# Dice_RGB_-_Sht_2.net
KiCad netlist of a schematic drawn in Altium Designer
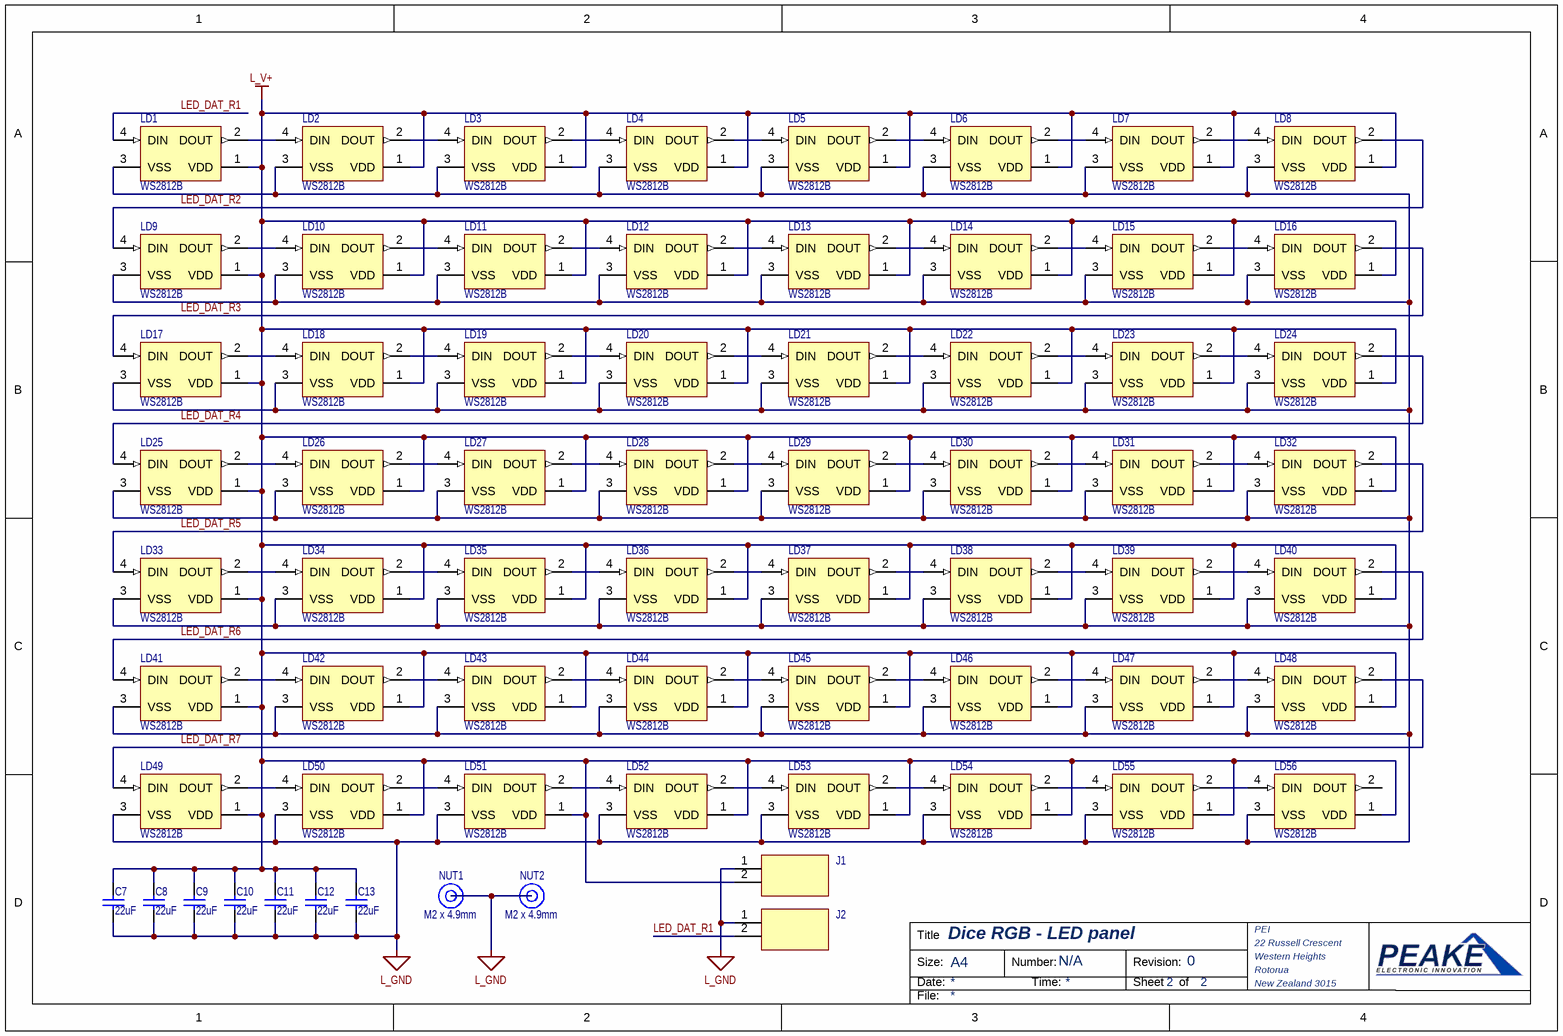
[diagram p0: Dice RGB - Sht 2.SchDoc]

(export (version "E")
  (design (tool "Eeschema 10.0.6"))
  (components
    (comp (ref "C7")
      (value "22uF")
      (footprint "0805_CAP")
      (description "SMD Capacitor")
      (fields (field (name "Comment") "Capacitor"))
      (libsource (lib "Peake Electronic Innovation") (part "Capacitor"))
    )
    (comp (ref "C8")
      (value "22uF")
      (footprint "0805_CAP")
      (description "SMD Capacitor")
      (fields (field (name "Comment") "Capacitor"))
      (libsource (lib "Peake Electronic Innovation") (part "Capacitor"))
    )
    (comp (ref "C9")
      (value "22uF")
      (footprint "0805_CAP")
      (description "SMD Capacitor")
      (fields (field (name "Comment") "Capacitor"))
      (libsource (lib "Peake Electronic Innovation") (part "Capacitor"))
    )
    (comp (ref "C10")
      (value "22uF")
      (footprint "0805_CAP")
      (description "SMD Capacitor")
      (fields (field (name "Comment") "Capacitor"))
      (libsource (lib "Peake Electronic Innovation") (part "Capacitor"))
    )
    (comp (ref "C11")
      (value "22uF")
      (footprint "0805_CAP")
      (description "SMD Capacitor")
      (fields (field (name "Comment") "Capacitor"))
      (libsource (lib "Peake Electronic Innovation") (part "Capacitor"))
    )
    (comp (ref "C12")
      (value "22uF")
      (footprint "0805_CAP")
      (description "SMD Capacitor")
      (fields (field (name "Comment") "Capacitor"))
      (libsource (lib "Peake Electronic Innovation") (part "Capacitor"))
    )
    (comp (ref "C13")
      (value "22uF")
      (footprint "0805_CAP")
      (description "SMD Capacitor")
      (fields (field (name "Comment") "Capacitor"))
      (libsource (lib "Peake Electronic Innovation") (part "Capacitor"))
    )
    (comp (ref "J1")
      (value "2_Pin")
      (footprint "2P 2mm SMD dbl height male header")
      (description "2 Pin Connector")
      (libsource (lib "Peake Electronic Innovation") (part "2_Pin"))
    )
    (comp (ref "J2")
      (value "2_Pin")
      (footprint "2P 2mm SMD dbl height male header")
      (description "2 Pin Connector")
      (libsource (lib "Peake Electronic Innovation") (part "2_Pin"))
    )
    (comp (ref "LD1")
      (value "WS2812B")
      (footprint "WS2812B-2020")
      (fields (field (name "MANUFACTURER") "Adafruit Industries"))
      (libsource (lib "Peake Electronic Innovation") (part "ADAI-WS2812B-4"))
    )
    (comp (ref "LD2")
      (value "WS2812B")
      (footprint "WS2812B-2020")
      (fields (field (name "MANUFACTURER") "Adafruit Industries"))
      (libsource (lib "Peake Electronic Innovation") (part "ADAI-WS2812B-4"))
    )
    (comp (ref "LD3")
      (value "WS2812B")
      (footprint "WS2812B-2020")
      (fields (field (name "MANUFACTURER") "Adafruit Industries"))
      (libsource (lib "Peake Electronic Innovation") (part "ADAI-WS2812B-4"))
    )
    (comp (ref "LD4")
      (value "WS2812B")
      (footprint "WS2812B-2020")
      (fields (field (name "MANUFACTURER") "Adafruit Industries"))
      (libsource (lib "Peake Electronic Innovation") (part "ADAI-WS2812B-4"))
    )
    (comp (ref "LD5")
      (value "WS2812B")
      (footprint "WS2812B-2020")
      (fields (field (name "MANUFACTURER") "Adafruit Industries"))
      (libsource (lib "Peake Electronic Innovation") (part "ADAI-WS2812B-4"))
    )
    (comp (ref "LD6")
      (value "WS2812B")
      (footprint "WS2812B-2020")
      (fields (field (name "MANUFACTURER") "Adafruit Industries"))
      (libsource (lib "Peake Electronic Innovation") (part "ADAI-WS2812B-4"))
    )
    (comp (ref "LD7")
      (value "WS2812B")
      (footprint "WS2812B-2020")
      (fields (field (name "MANUFACTURER") "Adafruit Industries"))
      (libsource (lib "Peake Electronic Innovation") (part "ADAI-WS2812B-4"))
    )
    (comp (ref "LD8")
      (value "WS2812B")
      (footprint "WS2812B-2020")
      (fields (field (name "MANUFACTURER") "Adafruit Industries"))
      (libsource (lib "Peake Electronic Innovation") (part "ADAI-WS2812B-4"))
    )
    (comp (ref "LD9")
      (value "WS2812B")
      (footprint "WS2812B-2020")
      (fields (field (name "MANUFACTURER") "Adafruit Industries"))
      (libsource (lib "Peake Electronic Innovation") (part "ADAI-WS2812B-4"))
    )
    (comp (ref "LD10")
      (value "WS2812B")
      (footprint "WS2812B-2020")
      (fields (field (name "MANUFACTURER") "Adafruit Industries"))
      (libsource (lib "Peake Electronic Innovation") (part "ADAI-WS2812B-4"))
    )
    (comp (ref "LD11")
      (value "WS2812B")
      (footprint "WS2812B-2020")
      (fields (field (name "MANUFACTURER") "Adafruit Industries"))
      (libsource (lib "Peake Electronic Innovation") (part "ADAI-WS2812B-4"))
    )
    (comp (ref "LD12")
      (value "WS2812B")
      (footprint "WS2812B-2020")
      (fields (field (name "MANUFACTURER") "Adafruit Industries"))
      (libsource (lib "Peake Electronic Innovation") (part "ADAI-WS2812B-4"))
    )
    (comp (ref "LD13")
      (value "WS2812B")
      (footprint "WS2812B-2020")
      (fields (field (name "MANUFACTURER") "Adafruit Industries"))
      (libsource (lib "Peake Electronic Innovation") (part "ADAI-WS2812B-4"))
    )
    (comp (ref "LD14")
      (value "WS2812B")
      (footprint "WS2812B-2020")
      (fields (field (name "MANUFACTURER") "Adafruit Industries"))
      (libsource (lib "Peake Electronic Innovation") (part "ADAI-WS2812B-4"))
    )
    (comp (ref "LD15")
      (value "WS2812B")
      (footprint "WS2812B-2020")
      (fields (field (name "MANUFACTURER") "Adafruit Industries"))
      (libsource (lib "Peake Electronic Innovation") (part "ADAI-WS2812B-4"))
    )
    (comp (ref "LD16")
      (value "WS2812B")
      (footprint "WS2812B-2020")
      (fields (field (name "MANUFACTURER") "Adafruit Industries"))
      (libsource (lib "Peake Electronic Innovation") (part "ADAI-WS2812B-4"))
    )
    (comp (ref "LD17")
      (value "WS2812B")
      (footprint "WS2812B-2020")
      (fields (field (name "MANUFACTURER") "Adafruit Industries"))
      (libsource (lib "Peake Electronic Innovation") (part "ADAI-WS2812B-4"))
    )
    (comp (ref "LD18")
      (value "WS2812B")
      (footprint "WS2812B-2020")
      (fields (field (name "MANUFACTURER") "Adafruit Industries"))
      (libsource (lib "Peake Electronic Innovation") (part "ADAI-WS2812B-4"))
    )
    (comp (ref "LD19")
      (value "WS2812B")
      (footprint "WS2812B-2020")
      (fields (field (name "MANUFACTURER") "Adafruit Industries"))
      (libsource (lib "Peake Electronic Innovation") (part "ADAI-WS2812B-4"))
    )
    (comp (ref "LD20")
      (value "WS2812B")
      (footprint "WS2812B-2020")
      (fields (field (name "MANUFACTURER") "Adafruit Industries"))
      (libsource (lib "Peake Electronic Innovation") (part "ADAI-WS2812B-4"))
    )
    (comp (ref "LD21")
      (value "WS2812B")
      (footprint "WS2812B-2020")
      (fields (field (name "MANUFACTURER") "Adafruit Industries"))
      (libsource (lib "Peake Electronic Innovation") (part "ADAI-WS2812B-4"))
    )
    (comp (ref "LD22")
      (value "WS2812B")
      (footprint "WS2812B-2020")
      (fields (field (name "MANUFACTURER") "Adafruit Industries"))
      (libsource (lib "Peake Electronic Innovation") (part "ADAI-WS2812B-4"))
    )
    (comp (ref "LD23")
      (value "WS2812B")
      (footprint "WS2812B-2020")
      (fields (field (name "MANUFACTURER") "Adafruit Industries"))
      (libsource (lib "Peake Electronic Innovation") (part "ADAI-WS2812B-4"))
    )
    (comp (ref "LD24")
      (value "WS2812B")
      (footprint "WS2812B-2020")
      (fields (field (name "MANUFACTURER") "Adafruit Industries"))
      (libsource (lib "Peake Electronic Innovation") (part "ADAI-WS2812B-4"))
    )
    (comp (ref "LD25")
      (value "WS2812B")
      (footprint "WS2812B-2020")
      (fields (field (name "MANUFACTURER") "Adafruit Industries"))
      (libsource (lib "Peake Electronic Innovation") (part "ADAI-WS2812B-4"))
    )
    (comp (ref "LD26")
      (value "WS2812B")
      (footprint "WS2812B-2020")
      (fields (field (name "MANUFACTURER") "Adafruit Industries"))
      (libsource (lib "Peake Electronic Innovation") (part "ADAI-WS2812B-4"))
    )
    (comp (ref "LD27")
      (value "WS2812B")
      (footprint "WS2812B-2020")
      (fields (field (name "MANUFACTURER") "Adafruit Industries"))
      (libsource (lib "Peake Electronic Innovation") (part "ADAI-WS2812B-4"))
    )
    (comp (ref "LD28")
      (value "WS2812B")
      (footprint "WS2812B-2020")
      (fields (field (name "MANUFACTURER") "Adafruit Industries"))
      (libsource (lib "Peake Electronic Innovation") (part "ADAI-WS2812B-4"))
    )
    (comp (ref "LD29")
      (value "WS2812B")
      (footprint "WS2812B-2020")
      (fields (field (name "MANUFACTURER") "Adafruit Industries"))
      (libsource (lib "Peake Electronic Innovation") (part "ADAI-WS2812B-4"))
    )
    (comp (ref "LD30")
      (value "WS2812B")
      (footprint "WS2812B-2020")
      (fields (field (name "MANUFACTURER") "Adafruit Industries"))
      (libsource (lib "Peake Electronic Innovation") (part "ADAI-WS2812B-4"))
    )
    (comp (ref "LD31")
      (value "WS2812B")
      (footprint "WS2812B-2020")
      (fields (field (name "MANUFACTURER") "Adafruit Industries"))
      (libsource (lib "Peake Electronic Innovation") (part "ADAI-WS2812B-4"))
    )
    (comp (ref "LD32")
      (value "WS2812B")
      (footprint "WS2812B-2020")
      (fields (field (name "MANUFACTURER") "Adafruit Industries"))
      (libsource (lib "Peake Electronic Innovation") (part "ADAI-WS2812B-4"))
    )
    (comp (ref "LD33")
      (value "WS2812B")
      (footprint "WS2812B-2020")
      (fields (field (name "MANUFACTURER") "Adafruit Industries"))
      (libsource (lib "Peake Electronic Innovation") (part "ADAI-WS2812B-4"))
    )
    (comp (ref "LD34")
      (value "WS2812B")
      (footprint "WS2812B-2020")
      (fields (field (name "MANUFACTURER") "Adafruit Industries"))
      (libsource (lib "Peake Electronic Innovation") (part "ADAI-WS2812B-4"))
    )
    (comp (ref "LD35")
      (value "WS2812B")
      (footprint "WS2812B-2020")
      (fields (field (name "MANUFACTURER") "Adafruit Industries"))
      (libsource (lib "Peake Electronic Innovation") (part "ADAI-WS2812B-4"))
    )
    (comp (ref "LD36")
      (value "WS2812B")
      (footprint "WS2812B-2020")
      (fields (field (name "MANUFACTURER") "Adafruit Industries"))
      (libsource (lib "Peake Electronic Innovation") (part "ADAI-WS2812B-4"))
    )
    (comp (ref "LD37")
      (value "WS2812B")
      (footprint "WS2812B-2020")
      (fields (field (name "MANUFACTURER") "Adafruit Industries"))
      (libsource (lib "Peake Electronic Innovation") (part "ADAI-WS2812B-4"))
    )
    (comp (ref "LD38")
      (value "WS2812B")
      (footprint "WS2812B-2020")
      (fields (field (name "MANUFACTURER") "Adafruit Industries"))
      (libsource (lib "Peake Electronic Innovation") (part "ADAI-WS2812B-4"))
    )
    (comp (ref "LD39")
      (value "WS2812B")
      (footprint "WS2812B-2020")
      (fields (field (name "MANUFACTURER") "Adafruit Industries"))
      (libsource (lib "Peake Electronic Innovation") (part "ADAI-WS2812B-4"))
    )
    (comp (ref "LD40")
      (value "WS2812B")
      (footprint "WS2812B-2020")
      (fields (field (name "MANUFACTURER") "Adafruit Industries"))
      (libsource (lib "Peake Electronic Innovation") (part "ADAI-WS2812B-4"))
    )
    (comp (ref "LD41")
      (value "WS2812B")
      (footprint "WS2812B-2020")
      (fields (field (name "MANUFACTURER") "Adafruit Industries"))
      (libsource (lib "Peake Electronic Innovation") (part "ADAI-WS2812B-4"))
    )
    (comp (ref "LD42")
      (value "WS2812B")
      (footprint "WS2812B-2020")
      (fields (field (name "MANUFACTURER") "Adafruit Industries"))
      (libsource (lib "Peake Electronic Innovation") (part "ADAI-WS2812B-4"))
    )
    (comp (ref "LD43")
      (value "WS2812B")
      (footprint "WS2812B-2020")
      (fields (field (name "MANUFACTURER") "Adafruit Industries"))
      (libsource (lib "Peake Electronic Innovation") (part "ADAI-WS2812B-4"))
    )
    (comp (ref "LD44")
      (value "WS2812B")
      (footprint "WS2812B-2020")
      (fields (field (name "MANUFACTURER") "Adafruit Industries"))
      (libsource (lib "Peake Electronic Innovation") (part "ADAI-WS2812B-4"))
    )
    (comp (ref "LD45")
      (value "WS2812B")
      (footprint "WS2812B-2020")
      (fields (field (name "MANUFACTURER") "Adafruit Industries"))
      (libsource (lib "Peake Electronic Innovation") (part "ADAI-WS2812B-4"))
    )
    (comp (ref "LD46")
      (value "WS2812B")
      (footprint "WS2812B-2020")
      (fields (field (name "MANUFACTURER") "Adafruit Industries"))
      (libsource (lib "Peake Electronic Innovation") (part "ADAI-WS2812B-4"))
    )
    (comp (ref "LD47")
      (value "WS2812B")
      (footprint "WS2812B-2020")
      (fields (field (name "MANUFACTURER") "Adafruit Industries"))
      (libsource (lib "Peake Electronic Innovation") (part "ADAI-WS2812B-4"))
    )
    (comp (ref "LD48")
      (value "WS2812B")
      (footprint "WS2812B-2020")
      (fields (field (name "MANUFACTURER") "Adafruit Industries"))
      (libsource (lib "Peake Electronic Innovation") (part "ADAI-WS2812B-4"))
    )
    (comp (ref "LD49")
      (value "WS2812B")
      (footprint "WS2812B-2020")
      (fields (field (name "MANUFACTURER") "Adafruit Industries"))
      (libsource (lib "Peake Electronic Innovation") (part "ADAI-WS2812B-4"))
    )
    (comp (ref "LD50")
      (value "WS2812B")
      (footprint "WS2812B-2020")
      (fields (field (name "MANUFACTURER") "Adafruit Industries"))
      (libsource (lib "Peake Electronic Innovation") (part "ADAI-WS2812B-4"))
    )
    (comp (ref "LD51")
      (value "WS2812B")
      (footprint "WS2812B-2020")
      (fields (field (name "MANUFACTURER") "Adafruit Industries"))
      (libsource (lib "Peake Electronic Innovation") (part "ADAI-WS2812B-4"))
    )
    (comp (ref "LD52")
      (value "WS2812B")
      (footprint "WS2812B-2020")
      (fields (field (name "MANUFACTURER") "Adafruit Industries"))
      (libsource (lib "Peake Electronic Innovation") (part "ADAI-WS2812B-4"))
    )
    (comp (ref "LD53")
      (value "WS2812B")
      (footprint "WS2812B-2020")
      (fields (field (name "MANUFACTURER") "Adafruit Industries"))
      (libsource (lib "Peake Electronic Innovation") (part "ADAI-WS2812B-4"))
    )
    (comp (ref "LD54")
      (value "WS2812B")
      (footprint "WS2812B-2020")
      (fields (field (name "MANUFACTURER") "Adafruit Industries"))
      (libsource (lib "Peake Electronic Innovation") (part "ADAI-WS2812B-4"))
    )
    (comp (ref "LD55")
      (value "WS2812B")
      (footprint "WS2812B-2020")
      (fields (field (name "MANUFACTURER") "Adafruit Industries"))
      (libsource (lib "Peake Electronic Innovation") (part "ADAI-WS2812B-4"))
    )
    (comp (ref "LD56")
      (value "WS2812B")
      (footprint "WS2812B-2020")
      (fields (field (name "MANUFACTURER") "Adafruit Industries"))
      (libsource (lib "Peake Electronic Innovation") (part "ADAI-WS2812B-4"))
    )
    (comp (ref "NUT1")
      (value "M2 x 4.9mm")
      (footprint "PCB Nut M2-SMD")
      (description "SMD or through hole soldered PCB nut")
      (libsource (lib "Peake Electronic Innovation") (part "PCB Nut-Symbol-1"))
    )
    (comp (ref "NUT2")
      (value "M2 x 4.9mm")
      (footprint "PCB Nut M2-SMD")
      (description "SMD or through hole soldered PCB nut")
      (libsource (lib "Peake Electronic Innovation") (part "PCB Nut-Symbol-1"))
    )
  )
  (nets
    (net (code "1") (name "/LED_DAT_R1") (class "Default")
      (node (ref "J2") (pin "2") (pinfunction "V+_2") (pintype "passive"))
      (node (ref "LD1") (pin "4") (pinfunction "DIN_4") (pintype "input"))
    )
    (net (code "2") (name "/LED_DAT_R2") (class "Default")
      (node (ref "LD8") (pin "2") (pinfunction "DOUT_2") (pintype "output"))
      (node (ref "LD9") (pin "4") (pinfunction "DIN_4") (pintype "input"))
    )
    (net (code "3") (name "/LED_DAT_R3") (class "Default")
      (node (ref "LD16") (pin "2") (pinfunction "DOUT_2") (pintype "output"))
      (node (ref "LD17") (pin "4") (pinfunction "DIN_4") (pintype "input"))
    )
    (net (code "4") (name "/LED_DAT_R4") (class "Default")
      (node (ref "LD24") (pin "2") (pinfunction "DOUT_2") (pintype "output"))
      (node (ref "LD25") (pin "4") (pinfunction "DIN_4") (pintype "input"))
    )
    (net (code "5") (name "/LED_DAT_R5") (class "Default")
      (node (ref "LD32") (pin "2") (pinfunction "DOUT_2") (pintype "output"))
      (node (ref "LD33") (pin "4") (pinfunction "DIN_4") (pintype "input"))
    )
    (net (code "6") (name "/LED_DAT_R6") (class "Default")
      (node (ref "LD40") (pin "2") (pinfunction "DOUT_2") (pintype "output"))
      (node (ref "LD41") (pin "4") (pinfunction "DIN_4") (pintype "input"))
    )
    (net (code "7") (name "/LED_DAT_R7") (class "Default")
      (node (ref "LD48") (pin "2") (pinfunction "DOUT_2") (pintype "output"))
      (node (ref "LD49") (pin "4") (pinfunction "DIN_4") (pintype "input"))
    )
    (net (code "8") (name "L_GND") (class "Default")
      (node (ref "C10") (pin "1") (pinfunction "1_1") (pintype "passive"))
      (node (ref "C11") (pin "1") (pinfunction "1_1") (pintype "passive"))
      (node (ref "C12") (pin "1") (pinfunction "1_1") (pintype "passive"))
      (node (ref "C13") (pin "1") (pinfunction "1_1") (pintype "passive"))
      (node (ref "C7") (pin "1") (pinfunction "1_1") (pintype "passive"))
      (node (ref "C8") (pin "1") (pinfunction "1_1") (pintype "passive"))
      (node (ref "C9") (pin "1") (pinfunction "1_1") (pintype "passive"))
      (node (ref "J1") (pin "1") (pinfunction "GND_1") (pintype "passive"))
      (node (ref "J2") (pin "1") (pinfunction "GND_1") (pintype "passive"))
      (node (ref "LD1") (pin "3") (pinfunction "VSS_3") (pintype "power_in"))
      (node (ref "LD10") (pin "3") (pinfunction "VSS_3") (pintype "power_in"))
      (node (ref "LD11") (pin "3") (pinfunction "VSS_3") (pintype "power_in"))
      (node (ref "LD12") (pin "3") (pinfunction "VSS_3") (pintype "power_in"))
      (node (ref "LD13") (pin "3") (pinfunction "VSS_3") (pintype "power_in"))
      (node (ref "LD14") (pin "3") (pinfunction "VSS_3") (pintype "power_in"))
      (node (ref "LD15") (pin "3") (pinfunction "VSS_3") (pintype "power_in"))
      (node (ref "LD16") (pin "3") (pinfunction "VSS_3") (pintype "power_in"))
      (node (ref "LD17") (pin "3") (pinfunction "VSS_3") (pintype "power_in"))
      (node (ref "LD18") (pin "3") (pinfunction "VSS_3") (pintype "power_in"))
      (node (ref "LD19") (pin "3") (pinfunction "VSS_3") (pintype "power_in"))
      (node (ref "LD2") (pin "3") (pinfunction "VSS_3") (pintype "power_in"))
      (node (ref "LD20") (pin "3") (pinfunction "VSS_3") (pintype "power_in"))
      (node (ref "LD21") (pin "3") (pinfunction "VSS_3") (pintype "power_in"))
      (node (ref "LD22") (pin "3") (pinfunction "VSS_3") (pintype "power_in"))
      (node (ref "LD23") (pin "3") (pinfunction "VSS_3") (pintype "power_in"))
      (node (ref "LD24") (pin "3") (pinfunction "VSS_3") (pintype "power_in"))
      (node (ref "LD25") (pin "3") (pinfunction "VSS_3") (pintype "power_in"))
      (node (ref "LD26") (pin "3") (pinfunction "VSS_3") (pintype "power_in"))
      (node (ref "LD27") (pin "3") (pinfunction "VSS_3") (pintype "power_in"))
      (node (ref "LD28") (pin "3") (pinfunction "VSS_3") (pintype "power_in"))
      (node (ref "LD29") (pin "3") (pinfunction "VSS_3") (pintype "power_in"))
      (node (ref "LD3") (pin "3") (pinfunction "VSS_3") (pintype "power_in"))
      (node (ref "LD30") (pin "3") (pinfunction "VSS_3") (pintype "power_in"))
      (node (ref "LD31") (pin "3") (pinfunction "VSS_3") (pintype "power_in"))
      (node (ref "LD32") (pin "3") (pinfunction "VSS_3") (pintype "power_in"))
      (node (ref "LD33") (pin "3") (pinfunction "VSS_3") (pintype "power_in"))
      (node (ref "LD34") (pin "3") (pinfunction "VSS_3") (pintype "power_in"))
      (node (ref "LD35") (pin "3") (pinfunction "VSS_3") (pintype "power_in"))
      (node (ref "LD36") (pin "3") (pinfunction "VSS_3") (pintype "power_in"))
      (node (ref "LD37") (pin "3") (pinfunction "VSS_3") (pintype "power_in"))
      (node (ref "LD38") (pin "3") (pinfunction "VSS_3") (pintype "power_in"))
      (node (ref "LD39") (pin "3") (pinfunction "VSS_3") (pintype "power_in"))
      (node (ref "LD4") (pin "3") (pinfunction "VSS_3") (pintype "power_in"))
      (node (ref "LD40") (pin "3") (pinfunction "VSS_3") (pintype "power_in"))
      (node (ref "LD41") (pin "3") (pinfunction "VSS_3") (pintype "power_in"))
      (node (ref "LD42") (pin "3") (pinfunction "VSS_3") (pintype "power_in"))
      (node (ref "LD43") (pin "3") (pinfunction "VSS_3") (pintype "power_in"))
      (node (ref "LD44") (pin "3") (pinfunction "VSS_3") (pintype "power_in"))
      (node (ref "LD45") (pin "3") (pinfunction "VSS_3") (pintype "power_in"))
      (node (ref "LD46") (pin "3") (pinfunction "VSS_3") (pintype "power_in"))
      (node (ref "LD47") (pin "3") (pinfunction "VSS_3") (pintype "power_in"))
      (node (ref "LD48") (pin "3") (pinfunction "VSS_3") (pintype "power_in"))
      (node (ref "LD49") (pin "3") (pinfunction "VSS_3") (pintype "power_in"))
      (node (ref "LD5") (pin "3") (pinfunction "VSS_3") (pintype "power_in"))
      (node (ref "LD50") (pin "3") (pinfunction "VSS_3") (pintype "power_in"))
      (node (ref "LD51") (pin "3") (pinfunction "VSS_3") (pintype "power_in"))
      (node (ref "LD52") (pin "3") (pinfunction "VSS_3") (pintype "power_in"))
      (node (ref "LD53") (pin "3") (pinfunction "VSS_3") (pintype "power_in"))
      (node (ref "LD54") (pin "3") (pinfunction "VSS_3") (pintype "power_in"))
      (node (ref "LD55") (pin "3") (pinfunction "VSS_3") (pintype "power_in"))
      (node (ref "LD56") (pin "3") (pinfunction "VSS_3") (pintype "power_in"))
      (node (ref "LD6") (pin "3") (pinfunction "VSS_3") (pintype "power_in"))
      (node (ref "LD7") (pin "3") (pinfunction "VSS_3") (pintype "power_in"))
      (node (ref "LD8") (pin "3") (pinfunction "VSS_3") (pintype "power_in"))
      (node (ref "LD9") (pin "3") (pinfunction "VSS_3") (pintype "power_in"))
      (node (ref "NUT1") (pin "1") (pintype "passive"))
      (node (ref "NUT2") (pin "1") (pintype "passive"))
    )
    (net (code "9") (name "L_V+") (class "Default")
      (node (ref "C10") (pin "2") (pinfunction "2_2") (pintype "passive"))
      (node (ref "C11") (pin "2") (pinfunction "2_2") (pintype "passive"))
      (node (ref "C12") (pin "2") (pinfunction "2_2") (pintype "passive"))
      (node (ref "C13") (pin "2") (pinfunction "2_2") (pintype "passive"))
      (node (ref "C7") (pin "2") (pinfunction "2_2") (pintype "passive"))
      (node (ref "C8") (pin "2") (pinfunction "2_2") (pintype "passive"))
      (node (ref "C9") (pin "2") (pinfunction "2_2") (pintype "passive"))
      (node (ref "J1") (pin "2") (pinfunction "V+_2") (pintype "passive"))
      (node (ref "LD1") (pin "1") (pinfunction "VDD_1") (pintype "power_in"))
      (node (ref "LD10") (pin "1") (pinfunction "VDD_1") (pintype "power_in"))
      (node (ref "LD11") (pin "1") (pinfunction "VDD_1") (pintype "power_in"))
      (node (ref "LD12") (pin "1") (pinfunction "VDD_1") (pintype "power_in"))
      (node (ref "LD13") (pin "1") (pinfunction "VDD_1") (pintype "power_in"))
      (node (ref "LD14") (pin "1") (pinfunction "VDD_1") (pintype "power_in"))
      (node (ref "LD15") (pin "1") (pinfunction "VDD_1") (pintype "power_in"))
      (node (ref "LD16") (pin "1") (pinfunction "VDD_1") (pintype "power_in"))
      (node (ref "LD17") (pin "1") (pinfunction "VDD_1") (pintype "power_in"))
      (node (ref "LD18") (pin "1") (pinfunction "VDD_1") (pintype "power_in"))
      (node (ref "LD19") (pin "1") (pinfunction "VDD_1") (pintype "power_in"))
      (node (ref "LD2") (pin "1") (pinfunction "VDD_1") (pintype "power_in"))
      (node (ref "LD20") (pin "1") (pinfunction "VDD_1") (pintype "power_in"))
      (node (ref "LD21") (pin "1") (pinfunction "VDD_1") (pintype "power_in"))
      (node (ref "LD22") (pin "1") (pinfunction "VDD_1") (pintype "power_in"))
      (node (ref "LD23") (pin "1") (pinfunction "VDD_1") (pintype "power_in"))
      (node (ref "LD24") (pin "1") (pinfunction "VDD_1") (pintype "power_in"))
      (node (ref "LD25") (pin "1") (pinfunction "VDD_1") (pintype "power_in"))
      (node (ref "LD26") (pin "1") (pinfunction "VDD_1") (pintype "power_in"))
      (node (ref "LD27") (pin "1") (pinfunction "VDD_1") (pintype "power_in"))
      (node (ref "LD28") (pin "1") (pinfunction "VDD_1") (pintype "power_in"))
      (node (ref "LD29") (pin "1") (pinfunction "VDD_1") (pintype "power_in"))
      (node (ref "LD3") (pin "1") (pinfunction "VDD_1") (pintype "power_in"))
      (node (ref "LD30") (pin "1") (pinfunction "VDD_1") (pintype "power_in"))
      (node (ref "LD31") (pin "1") (pinfunction "VDD_1") (pintype "power_in"))
      (node (ref "LD32") (pin "1") (pinfunction "VDD_1") (pintype "power_in"))
      (node (ref "LD33") (pin "1") (pinfunction "VDD_1") (pintype "power_in"))
      (node (ref "LD34") (pin "1") (pinfunction "VDD_1") (pintype "power_in"))
      (node (ref "LD35") (pin "1") (pinfunction "VDD_1") (pintype "power_in"))
      (node (ref "LD36") (pin "1") (pinfunction "VDD_1") (pintype "power_in"))
      (node (ref "LD37") (pin "1") (pinfunction "VDD_1") (pintype "power_in"))
      (node (ref "LD38") (pin "1") (pinfunction "VDD_1") (pintype "power_in"))
      (node (ref "LD39") (pin "1") (pinfunction "VDD_1") (pintype "power_in"))
      (node (ref "LD4") (pin "1") (pinfunction "VDD_1") (pintype "power_in"))
      (node (ref "LD40") (pin "1") (pinfunction "VDD_1") (pintype "power_in"))
      (node (ref "LD41") (pin "1") (pinfunction "VDD_1") (pintype "power_in"))
      (node (ref "LD42") (pin "1") (pinfunction "VDD_1") (pintype "power_in"))
      (node (ref "LD43") (pin "1") (pinfunction "VDD_1") (pintype "power_in"))
      (node (ref "LD44") (pin "1") (pinfunction "VDD_1") (pintype "power_in"))
      (node (ref "LD45") (pin "1") (pinfunction "VDD_1") (pintype "power_in"))
      (node (ref "LD46") (pin "1") (pinfunction "VDD_1") (pintype "power_in"))
      (node (ref "LD47") (pin "1") (pinfunction "VDD_1") (pintype "power_in"))
      (node (ref "LD48") (pin "1") (pinfunction "VDD_1") (pintype "power_in"))
      (node (ref "LD49") (pin "1") (pinfunction "VDD_1") (pintype "power_in"))
      (node (ref "LD5") (pin "1") (pinfunction "VDD_1") (pintype "power_in"))
      (node (ref "LD50") (pin "1") (pinfunction "VDD_1") (pintype "power_in"))
      (node (ref "LD51") (pin "1") (pinfunction "VDD_1") (pintype "power_in"))
      (node (ref "LD52") (pin "1") (pinfunction "VDD_1") (pintype "power_in"))
      (node (ref "LD53") (pin "1") (pinfunction "VDD_1") (pintype "power_in"))
      (node (ref "LD54") (pin "1") (pinfunction "VDD_1") (pintype "power_in"))
      (node (ref "LD55") (pin "1") (pinfunction "VDD_1") (pintype "power_in"))
      (node (ref "LD56") (pin "1") (pinfunction "VDD_1") (pintype "power_in"))
      (node (ref "LD6") (pin "1") (pinfunction "VDD_1") (pintype "power_in"))
      (node (ref "LD7") (pin "1") (pinfunction "VDD_1") (pintype "power_in"))
      (node (ref "LD8") (pin "1") (pinfunction "VDD_1") (pintype "power_in"))
      (node (ref "LD9") (pin "1") (pinfunction "VDD_1") (pintype "power_in"))
    )
    (net (code "10") (name "Net-(LD1-DOUT)") (class "Default")
      (node (ref "LD1") (pin "2") (pinfunction "DOUT_2") (pintype "output"))
      (node (ref "LD2") (pin "4") (pinfunction "DIN_4") (pintype "input"))
    )
    (net (code "11") (name "Net-(LD2-DOUT)") (class "Default")
      (node (ref "LD2") (pin "2") (pinfunction "DOUT_2") (pintype "output"))
      (node (ref "LD3") (pin "4") (pinfunction "DIN_4") (pintype "input"))
    )
    (net (code "12") (name "Net-(LD3-DOUT)") (class "Default")
      (node (ref "LD3") (pin "2") (pinfunction "DOUT_2") (pintype "output"))
      (node (ref "LD4") (pin "4") (pinfunction "DIN_4") (pintype "input"))
    )
    (net (code "13") (name "Net-(LD4-DOUT)") (class "Default")
      (node (ref "LD4") (pin "2") (pinfunction "DOUT_2") (pintype "output"))
      (node (ref "LD5") (pin "4") (pinfunction "DIN_4") (pintype "input"))
    )
    (net (code "14") (name "Net-(LD5-DOUT)") (class "Default")
      (node (ref "LD5") (pin "2") (pinfunction "DOUT_2") (pintype "output"))
      (node (ref "LD6") (pin "4") (pinfunction "DIN_4") (pintype "input"))
    )
    (net (code "15") (name "Net-(LD6-DOUT)") (class "Default")
      (node (ref "LD6") (pin "2") (pinfunction "DOUT_2") (pintype "output"))
      (node (ref "LD7") (pin "4") (pinfunction "DIN_4") (pintype "input"))
    )
    (net (code "16") (name "Net-(LD7-DOUT)") (class "Default")
      (node (ref "LD7") (pin "2") (pinfunction "DOUT_2") (pintype "output"))
      (node (ref "LD8") (pin "4") (pinfunction "DIN_4") (pintype "input"))
    )
    (net (code "17") (name "Net-(LD10-DIN)") (class "Default")
      (node (ref "LD10") (pin "4") (pinfunction "DIN_4") (pintype "input"))
      (node (ref "LD9") (pin "2") (pinfunction "DOUT_2") (pintype "output"))
    )
    (net (code "18") (name "Net-(LD10-DOUT)") (class "Default")
      (node (ref "LD10") (pin "2") (pinfunction "DOUT_2") (pintype "output"))
      (node (ref "LD11") (pin "4") (pinfunction "DIN_4") (pintype "input"))
    )
    (net (code "19") (name "Net-(LD11-DOUT)") (class "Default")
      (node (ref "LD11") (pin "2") (pinfunction "DOUT_2") (pintype "output"))
      (node (ref "LD12") (pin "4") (pinfunction "DIN_4") (pintype "input"))
    )
    (net (code "20") (name "Net-(LD12-DOUT)") (class "Default")
      (node (ref "LD12") (pin "2") (pinfunction "DOUT_2") (pintype "output"))
      (node (ref "LD13") (pin "4") (pinfunction "DIN_4") (pintype "input"))
    )
    (net (code "21") (name "Net-(LD13-DOUT)") (class "Default")
      (node (ref "LD13") (pin "2") (pinfunction "DOUT_2") (pintype "output"))
      (node (ref "LD14") (pin "4") (pinfunction "DIN_4") (pintype "input"))
    )
    (net (code "22") (name "Net-(LD14-DOUT)") (class "Default")
      (node (ref "LD14") (pin "2") (pinfunction "DOUT_2") (pintype "output"))
      (node (ref "LD15") (pin "4") (pinfunction "DIN_4") (pintype "input"))
    )
    (net (code "23") (name "Net-(LD15-DOUT)") (class "Default")
      (node (ref "LD15") (pin "2") (pinfunction "DOUT_2") (pintype "output"))
      (node (ref "LD16") (pin "4") (pinfunction "DIN_4") (pintype "input"))
    )
    (net (code "24") (name "Net-(LD17-DOUT)") (class "Default")
      (node (ref "LD17") (pin "2") (pinfunction "DOUT_2") (pintype "output"))
      (node (ref "LD18") (pin "4") (pinfunction "DIN_4") (pintype "input"))
    )
    (net (code "25") (name "Net-(LD18-DOUT)") (class "Default")
      (node (ref "LD18") (pin "2") (pinfunction "DOUT_2") (pintype "output"))
      (node (ref "LD19") (pin "4") (pinfunction "DIN_4") (pintype "input"))
    )
    (net (code "26") (name "Net-(LD19-DOUT)") (class "Default")
      (node (ref "LD19") (pin "2") (pinfunction "DOUT_2") (pintype "output"))
      (node (ref "LD20") (pin "4") (pinfunction "DIN_4") (pintype "input"))
    )
    (net (code "27") (name "Net-(LD20-DOUT)") (class "Default")
      (node (ref "LD20") (pin "2") (pinfunction "DOUT_2") (pintype "output"))
      (node (ref "LD21") (pin "4") (pinfunction "DIN_4") (pintype "input"))
    )
    (net (code "28") (name "Net-(LD21-DOUT)") (class "Default")
      (node (ref "LD21") (pin "2") (pinfunction "DOUT_2") (pintype "output"))
      (node (ref "LD22") (pin "4") (pinfunction "DIN_4") (pintype "input"))
    )
    (net (code "29") (name "Net-(LD22-DOUT)") (class "Default")
      (node (ref "LD22") (pin "2") (pinfunction "DOUT_2") (pintype "output"))
      (node (ref "LD23") (pin "4") (pinfunction "DIN_4") (pintype "input"))
    )
    (net (code "30") (name "Net-(LD23-DOUT)") (class "Default")
      (node (ref "LD23") (pin "2") (pinfunction "DOUT_2") (pintype "output"))
      (node (ref "LD24") (pin "4") (pinfunction "DIN_4") (pintype "input"))
    )
    (net (code "31") (name "Net-(LD25-DOUT)") (class "Default")
      (node (ref "LD25") (pin "2") (pinfunction "DOUT_2") (pintype "output"))
      (node (ref "LD26") (pin "4") (pinfunction "DIN_4") (pintype "input"))
    )
    (net (code "32") (name "Net-(LD26-DOUT)") (class "Default")
      (node (ref "LD26") (pin "2") (pinfunction "DOUT_2") (pintype "output"))
      (node (ref "LD27") (pin "4") (pinfunction "DIN_4") (pintype "input"))
    )
    (net (code "33") (name "Net-(LD27-DOUT)") (class "Default")
      (node (ref "LD27") (pin "2") (pinfunction "DOUT_2") (pintype "output"))
      (node (ref "LD28") (pin "4") (pinfunction "DIN_4") (pintype "input"))
    )
    (net (code "34") (name "Net-(LD28-DOUT)") (class "Default")
      (node (ref "LD28") (pin "2") (pinfunction "DOUT_2") (pintype "output"))
      (node (ref "LD29") (pin "4") (pinfunction "DIN_4") (pintype "input"))
    )
    (net (code "35") (name "Net-(LD29-DOUT)") (class "Default")
      (node (ref "LD29") (pin "2") (pinfunction "DOUT_2") (pintype "output"))
      (node (ref "LD30") (pin "4") (pinfunction "DIN_4") (pintype "input"))
    )
    (net (code "36") (name "Net-(LD30-DOUT)") (class "Default")
      (node (ref "LD30") (pin "2") (pinfunction "DOUT_2") (pintype "output"))
      (node (ref "LD31") (pin "4") (pinfunction "DIN_4") (pintype "input"))
    )
    (net (code "37") (name "Net-(LD31-DOUT)") (class "Default")
      (node (ref "LD31") (pin "2") (pinfunction "DOUT_2") (pintype "output"))
      (node (ref "LD32") (pin "4") (pinfunction "DIN_4") (pintype "input"))
    )
    (net (code "38") (name "Net-(LD33-DOUT)") (class "Default")
      (node (ref "LD33") (pin "2") (pinfunction "DOUT_2") (pintype "output"))
      (node (ref "LD34") (pin "4") (pinfunction "DIN_4") (pintype "input"))
    )
    (net (code "39") (name "Net-(LD34-DOUT)") (class "Default")
      (node (ref "LD34") (pin "2") (pinfunction "DOUT_2") (pintype "output"))
      (node (ref "LD35") (pin "4") (pinfunction "DIN_4") (pintype "input"))
    )
    (net (code "40") (name "Net-(LD35-DOUT)") (class "Default")
      (node (ref "LD35") (pin "2") (pinfunction "DOUT_2") (pintype "output"))
      (node (ref "LD36") (pin "4") (pinfunction "DIN_4") (pintype "input"))
    )
    (net (code "41") (name "Net-(LD36-DOUT)") (class "Default")
      (node (ref "LD36") (pin "2") (pinfunction "DOUT_2") (pintype "output"))
      (node (ref "LD37") (pin "4") (pinfunction "DIN_4") (pintype "input"))
    )
    (net (code "42") (name "Net-(LD37-DOUT)") (class "Default")
      (node (ref "LD37") (pin "2") (pinfunction "DOUT_2") (pintype "output"))
      (node (ref "LD38") (pin "4") (pinfunction "DIN_4") (pintype "input"))
    )
    (net (code "43") (name "Net-(LD38-DOUT)") (class "Default")
      (node (ref "LD38") (pin "2") (pinfunction "DOUT_2") (pintype "output"))
      (node (ref "LD39") (pin "4") (pinfunction "DIN_4") (pintype "input"))
    )
    (net (code "44") (name "Net-(LD39-DOUT)") (class "Default")
      (node (ref "LD39") (pin "2") (pinfunction "DOUT_2") (pintype "output"))
      (node (ref "LD40") (pin "4") (pinfunction "DIN_4") (pintype "input"))
    )
    (net (code "45") (name "Net-(LD41-DOUT)") (class "Default")
      (node (ref "LD41") (pin "2") (pinfunction "DOUT_2") (pintype "output"))
      (node (ref "LD42") (pin "4") (pinfunction "DIN_4") (pintype "input"))
    )
    (net (code "46") (name "Net-(LD42-DOUT)") (class "Default")
      (node (ref "LD42") (pin "2") (pinfunction "DOUT_2") (pintype "output"))
      (node (ref "LD43") (pin "4") (pinfunction "DIN_4") (pintype "input"))
    )
    (net (code "47") (name "Net-(LD43-DOUT)") (class "Default")
      (node (ref "LD43") (pin "2") (pinfunction "DOUT_2") (pintype "output"))
      (node (ref "LD44") (pin "4") (pinfunction "DIN_4") (pintype "input"))
    )
    (net (code "48") (name "Net-(LD44-DOUT)") (class "Default")
      (node (ref "LD44") (pin "2") (pinfunction "DOUT_2") (pintype "output"))
      (node (ref "LD45") (pin "4") (pinfunction "DIN_4") (pintype "input"))
    )
    (net (code "49") (name "Net-(LD45-DOUT)") (class "Default")
      (node (ref "LD45") (pin "2") (pinfunction "DOUT_2") (pintype "output"))
      (node (ref "LD46") (pin "4") (pinfunction "DIN_4") (pintype "input"))
    )
    (net (code "50") (name "Net-(LD46-DOUT)") (class "Default")
      (node (ref "LD46") (pin "2") (pinfunction "DOUT_2") (pintype "output"))
      (node (ref "LD47") (pin "4") (pinfunction "DIN_4") (pintype "input"))
    )
    (net (code "51") (name "Net-(LD47-DOUT)") (class "Default")
      (node (ref "LD47") (pin "2") (pinfunction "DOUT_2") (pintype "output"))
      (node (ref "LD48") (pin "4") (pinfunction "DIN_4") (pintype "input"))
    )
    (net (code "52") (name "Net-(LD49-DOUT)") (class "Default")
      (node (ref "LD49") (pin "2") (pinfunction "DOUT_2") (pintype "output"))
      (node (ref "LD50") (pin "4") (pinfunction "DIN_4") (pintype "input"))
    )
    (net (code "53") (name "Net-(LD50-DOUT)") (class "Default")
      (node (ref "LD50") (pin "2") (pinfunction "DOUT_2") (pintype "output"))
      (node (ref "LD51") (pin "4") (pinfunction "DIN_4") (pintype "input"))
    )
    (net (code "54") (name "Net-(LD51-DOUT)") (class "Default")
      (node (ref "LD51") (pin "2") (pinfunction "DOUT_2") (pintype "output"))
      (node (ref "LD52") (pin "4") (pinfunction "DIN_4") (pintype "input"))
    )
    (net (code "55") (name "Net-(LD52-DOUT)") (class "Default")
      (node (ref "LD52") (pin "2") (pinfunction "DOUT_2") (pintype "output"))
      (node (ref "LD53") (pin "4") (pinfunction "DIN_4") (pintype "input"))
    )
    (net (code "56") (name "Net-(LD53-DOUT)") (class "Default")
      (node (ref "LD53") (pin "2") (pinfunction "DOUT_2") (pintype "output"))
      (node (ref "LD54") (pin "4") (pinfunction "DIN_4") (pintype "input"))
    )
    (net (code "57") (name "Net-(LD54-DOUT)") (class "Default")
      (node (ref "LD54") (pin "2") (pinfunction "DOUT_2") (pintype "output"))
      (node (ref "LD55") (pin "4") (pinfunction "DIN_4") (pintype "input"))
    )
    (net (code "58") (name "Net-(LD55-DOUT)") (class "Default")
      (node (ref "LD55") (pin "2") (pinfunction "DOUT_2") (pintype "output"))
      (node (ref "LD56") (pin "4") (pinfunction "DIN_4") (pintype "input"))
    )
    (net (code "59") (name "unconnected-(LD56-DOUT-Pad2)") (class "Default")
      (node (ref "LD56") (pin "2") (pinfunction "DOUT_2") (pintype "output"))
    )
  )
)
